# Antenna.net
KiCad netlist of a schematic drawn in Altium Designer
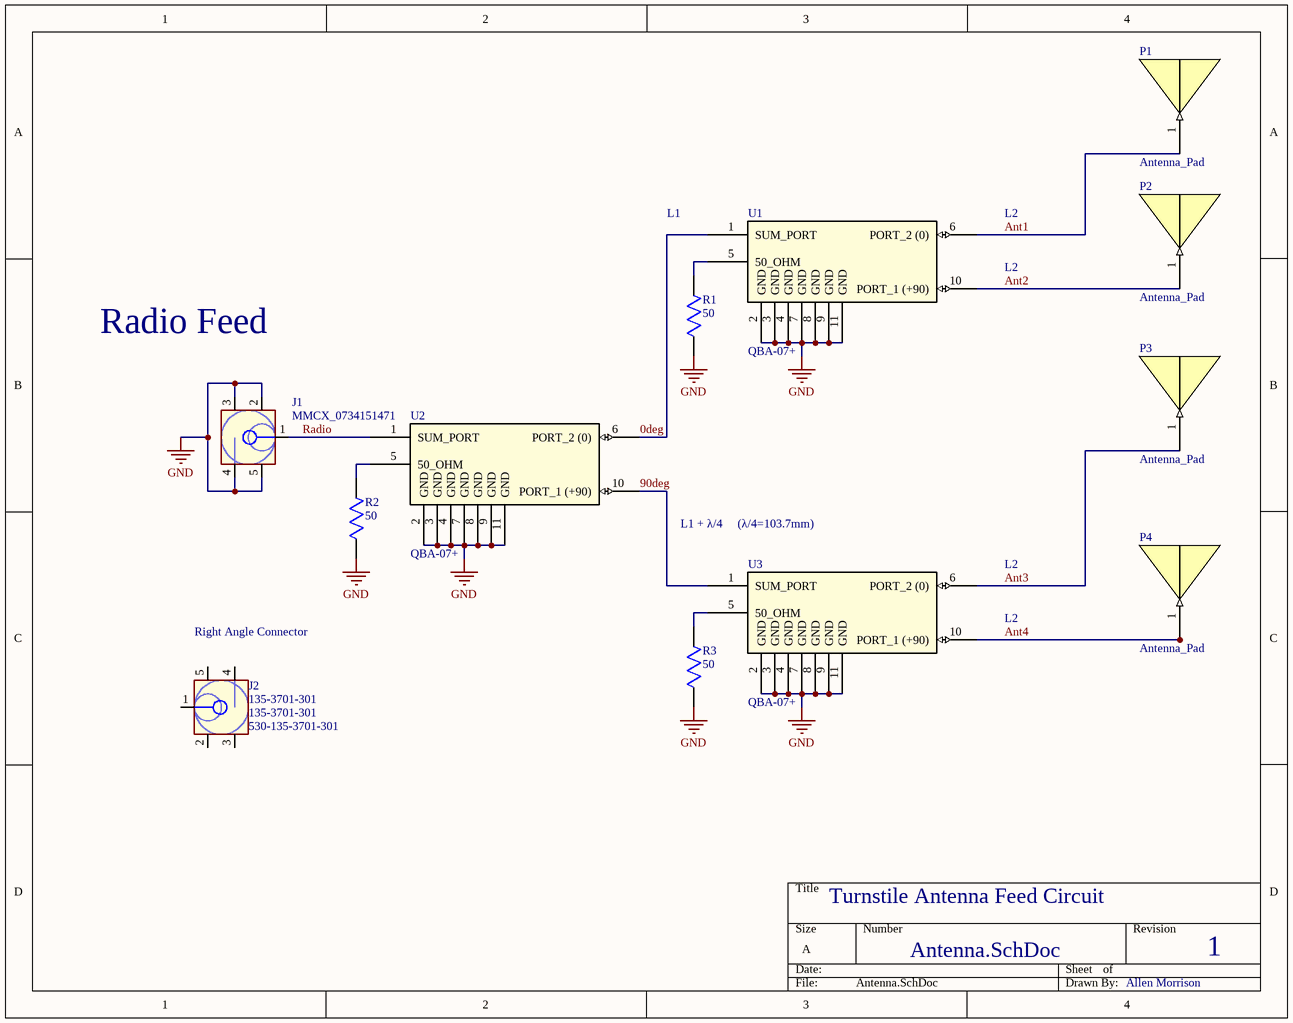
[diagram p0: Antenna.SchDoc]

(export (version "E")
  (design (tool "Eeschema 10.0.6"))
  (components
    (comp (ref "J1")
      (value "MMCX_0734151471")
      (footprint "MMCX_0734151471")
      (description "Conn MMCX RCP 50Ohm Solder ST Thru-Hole Gold Bulk")
      (fields (field (name "MANUFACTURER PART NUMBER") "73415-1471"))
      (libsource (lib "Antenna") (part "MMCX_Straight"))
    )
    (comp (ref "J2")
      (value "135-3701-301")
      (footprint "MMCX_0734151471")
      (fields
        (field (name "MANUFACTURER PART NUMBER") "135-3701-301")
        (field (name "SUPPLIER PART NUMBER 1") "530-135-3701-301")
      )
      (libsource (lib "Antenna") (part "MMCX_Right"))
    )
    (comp (ref "P1")
      (value "Antenna_Pad")
      (footprint "Antenna_Pad")
      (libsource (lib "Antenna") (part "Antenna_Pad"))
    )
    (comp (ref "P2")
      (value "Antenna_Pad")
      (footprint "Antenna_Pad")
      (libsource (lib "Antenna") (part "Antenna_Pad"))
    )
    (comp (ref "P3")
      (value "Antenna_Pad")
      (footprint "Antenna_Pad")
      (libsource (lib "Antenna") (part "Antenna_Pad"))
    )
    (comp (ref "P4")
      (value "Antenna_Pad")
      (footprint "Antenna_Pad")
      (libsource (lib "Antenna") (part "Antenna_Pad"))
    )
    (comp (ref "R1")
      (value "50")
      (description "50 Ohm Space Resistor")
      (fields
        (field (name "MANUFACTURER PART NUMBER") "311-430JRCT-ND")
        (field (name "MANUFACTURER") "Yageo")
      )
      (libsource (lib "Antenna") (part "RES_50_0603_1.5W"))
    )
    (comp (ref "R2")
      (value "50")
      (description "50 Ohm Space Resistor")
      (fields
        (field (name "MANUFACTURER PART NUMBER") "311-430JRCT-ND")
        (field (name "MANUFACTURER") "Yageo")
      )
      (libsource (lib "Antenna") (part "RES_50_0603_1.5W"))
    )
    (comp (ref "R3")
      (value "50")
      (description "50 Ohm Space Resistor")
      (fields
        (field (name "MANUFACTURER PART NUMBER") "311-430JRCT-ND")
        (field (name "MANUFACTURER") "Yageo")
      )
      (libsource (lib "Antenna") (part "RES_50_0603_1.5W"))
    )
    (comp (ref "U1")
      (value "QBA-07+")
      (footprint "SM1L_MNC")
      (description "No Description Available")
      (fields (field (name "COPYRIGHT") "Copyright (C) 2022 Ultra Librarian. All rights reserved."))
      (libsource (lib "Antenna") (part "QBA-07+"))
    )
    (comp (ref "U2")
      (value "QBA-07+")
      (footprint "SM1L_MNC")
      (description "No Description Available")
      (fields (field (name "COPYRIGHT") "Copyright (C) 2022 Ultra Librarian. All rights reserved."))
      (libsource (lib "Antenna") (part "QBA-07+"))
    )
    (comp (ref "U3")
      (value "QBA-07+")
      (footprint "SM1L_MNC")
      (description "No Description Available")
      (fields (field (name "COPYRIGHT") "Copyright (C) 2022 Ultra Librarian. All rights reserved."))
      (libsource (lib "Antenna") (part "QBA-07+"))
    )
  )
  (nets
    (net (code "1") (name "/0deg") (class "Default")
      (node (ref "U1") (pin "1") (pinfunction "SUM_PORT_1") (pintype "passive"))
      (node (ref "U2") (pin "6") (pinfunction "PORT_2_(0)_6") (pintype "bidirectional"))
    )
    (net (code "2") (name "/90deg") (class "Default")
      (node (ref "U2") (pin "10") (pinfunction "PORT_1_(+90)_10") (pintype "bidirectional"))
      (node (ref "U3") (pin "1") (pinfunction "SUM_PORT_1") (pintype "passive"))
    )
    (net (code "3") (name "/Ant1") (class "Default")
      (node (ref "P1") (pin "1") (pintype "input"))
      (node (ref "U1") (pin "6") (pinfunction "PORT_2_(0)_6") (pintype "bidirectional"))
    )
    (net (code "4") (name "/Ant2") (class "Default")
      (node (ref "P2") (pin "1") (pintype "input"))
      (node (ref "U1") (pin "10") (pinfunction "PORT_1_(+90)_10") (pintype "bidirectional"))
    )
    (net (code "5") (name "/Ant3") (class "Default")
      (node (ref "P3") (pin "1") (pintype "input"))
      (node (ref "U3") (pin "6") (pinfunction "PORT_2_(0)_6") (pintype "bidirectional"))
    )
    (net (code "6") (name "/Ant4") (class "Default")
      (node (ref "P4") (pin "1") (pintype "input"))
      (node (ref "U3") (pin "10") (pinfunction "PORT_1_(+90)_10") (pintype "bidirectional"))
    )
    (net (code "7") (name "/Radio") (class "Default")
      (node (ref "J1") (pin "1") (pinfunction "1_1") (pintype "passive"))
      (node (ref "U2") (pin "1") (pinfunction "SUM_PORT_1") (pintype "passive"))
    )
    (net (code "8") (name "GND") (class "Default")
      (node (ref "J1") (pin "2") (pinfunction "2_2") (pintype "passive"))
      (node (ref "J1") (pin "3") (pinfunction "3_3") (pintype "passive"))
      (node (ref "J1") (pin "4") (pinfunction "4_4") (pintype "passive"))
      (node (ref "J1") (pin "5") (pinfunction "5_5") (pintype "passive"))
      (node (ref "R1") (pin "1") (pinfunction "1_1") (pintype "passive"))
      (node (ref "R2") (pin "1") (pinfunction "1_1") (pintype "passive"))
      (node (ref "R3") (pin "1") (pinfunction "1_1") (pintype "passive"))
      (node (ref "U1") (pin "11") (pinfunction "GND_11") (pintype "passive"))
      (node (ref "U1") (pin "2") (pinfunction "GND_2") (pintype "passive"))
      (node (ref "U1") (pin "3") (pinfunction "GND_3") (pintype "passive"))
      (node (ref "U1") (pin "4") (pinfunction "GND_4") (pintype "passive"))
      (node (ref "U1") (pin "7") (pinfunction "GND_7") (pintype "passive"))
      (node (ref "U1") (pin "8") (pinfunction "GND_8") (pintype "passive"))
      (node (ref "U1") (pin "9") (pinfunction "GND_9") (pintype "passive"))
      (node (ref "U2") (pin "11") (pinfunction "GND_11") (pintype "passive"))
      (node (ref "U2") (pin "2") (pinfunction "GND_2") (pintype "passive"))
      (node (ref "U2") (pin "3") (pinfunction "GND_3") (pintype "passive"))
      (node (ref "U2") (pin "4") (pinfunction "GND_4") (pintype "passive"))
      (node (ref "U2") (pin "7") (pinfunction "GND_7") (pintype "passive"))
      (node (ref "U2") (pin "8") (pinfunction "GND_8") (pintype "passive"))
      (node (ref "U2") (pin "9") (pinfunction "GND_9") (pintype "passive"))
      (node (ref "U3") (pin "11") (pinfunction "GND_11") (pintype "passive"))
      (node (ref "U3") (pin "2") (pinfunction "GND_2") (pintype "passive"))
      (node (ref "U3") (pin "3") (pinfunction "GND_3") (pintype "passive"))
      (node (ref "U3") (pin "4") (pinfunction "GND_4") (pintype "passive"))
      (node (ref "U3") (pin "7") (pinfunction "GND_7") (pintype "passive"))
      (node (ref "U3") (pin "8") (pinfunction "GND_8") (pintype "passive"))
      (node (ref "U3") (pin "9") (pinfunction "GND_9") (pintype "passive"))
    )
    (net (code "9") (name "Net-(U1-50_OHM)") (class "Default")
      (node (ref "R1") (pin "2") (pinfunction "2_2") (pintype "passive"))
      (node (ref "U1") (pin "5") (pinfunction "50_OHM_5") (pintype "passive"))
    )
    (net (code "10") (name "Net-(U2-50_OHM)") (class "Default")
      (node (ref "R2") (pin "2") (pinfunction "2_2") (pintype "passive"))
      (node (ref "U2") (pin "5") (pinfunction "50_OHM_5") (pintype "passive"))
    )
    (net (code "11") (name "Net-(U3-50_OHM)") (class "Default")
      (node (ref "R3") (pin "2") (pinfunction "2_2") (pintype "passive"))
      (node (ref "U3") (pin "5") (pinfunction "50_OHM_5") (pintype "passive"))
    )
    (net (code "12") (name "unconnected-(J2-Pad1)") (class "Default")
      (node (ref "J2") (pin "1") (pinfunction "1_1") (pintype "passive"))
    )
    (net (code "13") (name "unconnected-(J2-Pad2)") (class "Default")
      (node (ref "J2") (pin "2") (pinfunction "2_2") (pintype "passive"))
    )
    (net (code "14") (name "unconnected-(J2-Pad3)") (class "Default")
      (node (ref "J2") (pin "3") (pinfunction "3_3") (pintype "passive"))
    )
    (net (code "15") (name "unconnected-(J2-Pad4)") (class "Default")
      (node (ref "J2") (pin "4") (pinfunction "4_4") (pintype "passive"))
    )
    (net (code "16") (name "unconnected-(J2-Pad5)") (class "Default")
      (node (ref "J2") (pin "5") (pinfunction "5_5") (pintype "passive"))
    )
  )
)
